# OnOfre_2ADSP.net
KiCad netlist of a schematic drawn in EAGLE
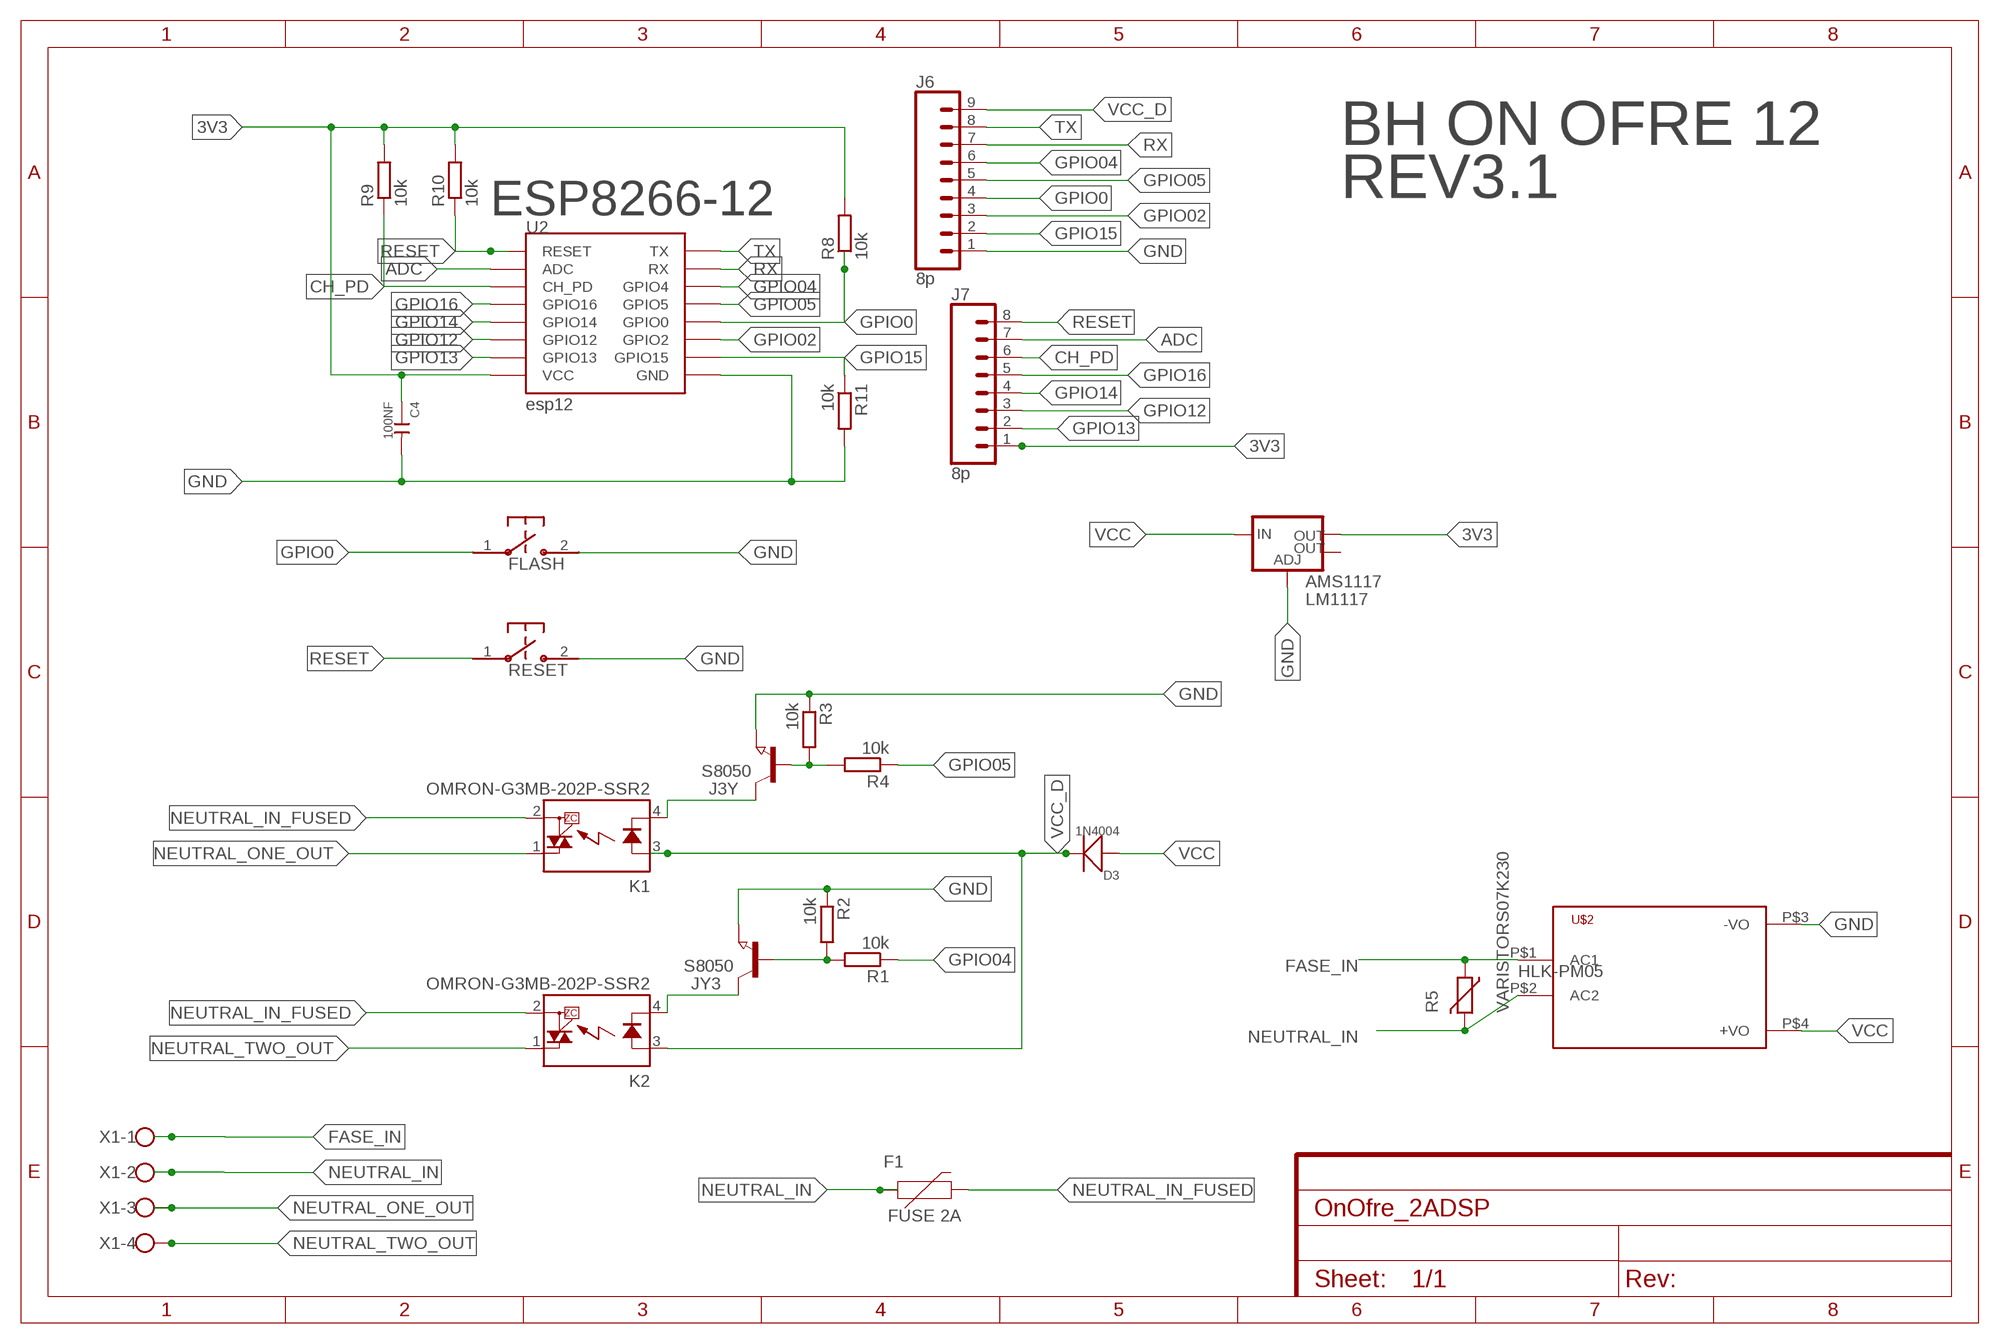
[diagram p0: schematic, sheet 1]

(export (version "E")
  (design (tool "Eeschema 10.0.6"))
  (components
    (comp (ref "AMS1117")
      (value "LM1117")
      (footprint "eagle-import:SOT223")
      (libsource (lib "eagle-import") (part "V_REG_LM1117SOT223"))
    )
    (comp (ref "C4")
      (value "100NF")
      (footprint "eagle-import:C1206")
      (fields (field (name "MPN") "CC1206KKX7RCBB102"))
      (libsource (lib "eagle-import") (part "CERAMIC-1NF-1KV-10%-X7R?(1206)"))
    )
    (comp (ref "D3")
      (value "1N4004")
      (footprint "eagle-import:DO-214AC")
      (fields (field (name "MPN") "1N4007"))
      (libsource (lib "eagle-import") (part "DIODE-GEN-PURPOSE-1KV-1A(DO-214AC)"))
    )
    (comp (ref "F1")
      (value "FUSE 2A")
      (footprint "eagle-import:PTH")
      (libsource (lib "eagle-import") (part "PPTC_PTH"))
    )
    (comp (ref "FLASH")
      (value "B3U-1000P-2P-SMD")
      (footprint "eagle-import:B3U-1000P")
      (fields
        (field (name "MANUFACTURER") "Omron")
        (field (name "MPN") "B3U-1000P")
        (field (name "SPICEPREFIX") "F")
      )
      (libsource (lib "eagle-import") (part "B3U-1000P"))
    )
    (comp (ref "J3Y")
      (value "S8050")
      (footprint "eagle-import:SOT23")
      (libsource (lib "eagle-import") (part "NPN-TRANSISTOR_SOT23"))
    )
    (comp (ref "J6")
      (value "8p")
      (footprint "eagle-import:1X09")
      (libsource (lib "eagle-import") (part "CONN_09"))
    )
    (comp (ref "J7")
      (value "8p")
      (footprint "eagle-import:1X08")
      (libsource (lib "eagle-import") (part "CONN_08{dblquote}"))
    )
    (comp (ref "JY3")
      (value "S8050")
      (footprint "eagle-import:SOT23")
      (libsource (lib "eagle-import") (part "NPN-TRANSISTOR_SOT23"))
    )
    (comp (ref "K1")
      (value "OMRON-G3MB-202P-SSR2")
      (footprint "eagle-import:OMRON-G3MB-202P-SSR")
      (fields (field (name "MPN") "S202S02F"))
      (libsource (lib "eagle-import") (part "OMRON-G3MB-202P-SSR2"))
    )
    (comp (ref "K2")
      (value "OMRON-G3MB-202P-SSR2")
      (footprint "eagle-import:OMRON-G3MB-202P-SSR")
      (fields (field (name "MPN") "S202S02F"))
      (libsource (lib "eagle-import") (part "OMRON-G3MB-202P-SSR2"))
    )
    (comp (ref "R1")
      (value "10k")
      (footprint "eagle-import:R0603")
      (libsource (lib "eagle-import") (part "R-EU_R0603"))
    )
    (comp (ref "R2")
      (value "10k")
      (footprint "eagle-import:R0603")
      (libsource (lib "eagle-import") (part "R-EU_R0603"))
    )
    (comp (ref "R3")
      (value "10k")
      (footprint "eagle-import:R0603")
      (libsource (lib "eagle-import") (part "R-EU_R0603"))
    )
    (comp (ref "R4")
      (value "10k")
      (footprint "eagle-import:R0603")
      (libsource (lib "eagle-import") (part "R-EU_R0603"))
    )
    (comp (ref "R5")
      (value "VARISTORS07K230")
      (footprint "eagle-import:S07K230")
      (libsource (lib "eagle-import") (part "VARISTORS07K230"))
    )
    (comp (ref "R8")
      (value "10k")
      (footprint "eagle-import:R0603")
      (libsource (lib "eagle-import") (part "R-EU_R0603"))
    )
    (comp (ref "R9")
      (value "10k")
      (footprint "eagle-import:R0603")
      (libsource (lib "eagle-import") (part "R-EU_R0603"))
    )
    (comp (ref "R10")
      (value "10k")
      (footprint "eagle-import:R0603")
      (libsource (lib "eagle-import") (part "R-EU_R0603"))
    )
    (comp (ref "R11")
      (value "10k")
      (footprint "eagle-import:R0603")
      (libsource (lib "eagle-import") (part "R-EU_R0603"))
    )
    (comp (ref "RESET")
      (value "B3U-1000P-2P-SMD")
      (footprint "eagle-import:B3U-1000P")
      (fields (field (name "MANUFACTURER") "Omron") (field (name "MPN") "B3U-1000P"))
      (libsource (lib "eagle-import") (part "B3U-1000P"))
    )
    (comp (ref "U$2")
      (value "HKLPM01")
      (footprint "eagle-import:HKLPM01")
      (libsource (lib "eagle-import") (part "HKLPM01"))
    )
    (comp (ref "U2")
      (value "esp12")
      (footprint "eagle-import:ESP12-SMD")
      (libsource (lib "eagle-import") (part "ESP12SMD"))
    )
    (comp (ref "X1")
      (value "W237-4")
      (footprint "eagle-import:W237-4")
      (libsource (lib "eagle-import") (part "W237-4"))
    )
  )
  (nets
    (net (code "1") (name "3V3") (class "Default")
      (node (ref "AMS1117") (pin "2") (pinfunction "OUT_2") (pintype "output"))
      (node (ref "C4") (pin "1") (pinfunction "1_1") (pintype "passive"))
      (node (ref "J7") (pin "1") (pinfunction "1_1") (pintype "passive"))
      (node (ref "R10") (pin "2") (pinfunction "2_2") (pintype "passive"))
      (node (ref "R8") (pin "2") (pinfunction "2_2") (pintype "passive"))
      (node (ref "R9") (pin "2") (pinfunction "2_2") (pintype "passive"))
      (node (ref "U2") (pin "VCC") (pinfunction "VCC_VCC") (pintype "bidirectional"))
    )
    (net (code "2") (name "ADC") (class "Default")
      (node (ref "J7") (pin "7") (pinfunction "7_7") (pintype "passive"))
      (node (ref "U2") (pin "ADC") (pinfunction "ADC_ADC") (pintype "bidirectional"))
    )
    (net (code "3") (name "CH_PD") (class "Default")
      (node (ref "J7") (pin "6") (pinfunction "6_6") (pintype "passive"))
      (node (ref "R9") (pin "1") (pinfunction "1_1") (pintype "passive"))
      (node (ref "U2") (pin "CH_PD") (pinfunction "CH_PD_CH_PD") (pintype "bidirectional"))
    )
    (net (code "4") (name "FASE_IN") (class "Default")
      (node (ref "R5") (pin "1") (pinfunction "1_1") (pintype "passive"))
      (node (ref "U$2") (pin "P$1") (pinfunction "AC1_P$1") (pintype "bidirectional"))
      (node (ref "X1") (pin "1") (pinfunction "KL_1") (pintype "passive"))
    )
    (net (code "5") (name "GND") (class "Default")
      (node (ref "AMS1117") (pin "1") (pinfunction "ADJ_1") (pintype "input"))
      (node (ref "C4") (pin "2") (pinfunction "2_2") (pintype "passive"))
      (node (ref "FLASH") (pin "2") (pinfunction "P$2_2") (pintype "passive"))
      (node (ref "J3Y") (pin "2") (pinfunction "E_2") (pintype "passive"))
      (node (ref "J6") (pin "1") (pinfunction "1_1") (pintype "passive"))
      (node (ref "JY3") (pin "2") (pinfunction "E_2") (pintype "passive"))
      (node (ref "R11") (pin "2") (pinfunction "2_2") (pintype "passive"))
      (node (ref "R2") (pin "1") (pinfunction "1_1") (pintype "passive"))
      (node (ref "R3") (pin "1") (pinfunction "1_1") (pintype "passive"))
      (node (ref "RESET") (pin "2") (pinfunction "P$2_2") (pintype "passive"))
      (node (ref "U$2") (pin "P$3") (pinfunction "-VO_P$3") (pintype "bidirectional"))
      (node (ref "U2") (pin "GND") (pinfunction "GND_GND") (pintype "bidirectional"))
    )
    (net (code "6") (name "GPIO0") (class "Default")
      (node (ref "FLASH") (pin "1") (pinfunction "P$1_1") (pintype "passive"))
      (node (ref "J6") (pin "4") (pinfunction "4_4") (pintype "passive"))
      (node (ref "R8") (pin "1") (pinfunction "1_1") (pintype "passive"))
      (node (ref "U2") (pin "GPIO0") (pinfunction "GPIO0_GPIO0") (pintype "bidirectional"))
    )
    (net (code "7") (name "GPIO02") (class "Default")
      (node (ref "J6") (pin "3") (pinfunction "3_3") (pintype "passive"))
      (node (ref "U2") (pin "GPIO2") (pinfunction "GPIO2_GPIO2") (pintype "bidirectional"))
    )
    (net (code "8") (name "GPIO04") (class "Default")
      (node (ref "J6") (pin "6") (pinfunction "6_6") (pintype "passive"))
      (node (ref "R1") (pin "1") (pinfunction "1_1") (pintype "passive"))
      (node (ref "U2") (pin "GPIO4") (pinfunction "GPIO4_GPIO4") (pintype "bidirectional"))
    )
    (net (code "9") (name "GPIO05") (class "Default")
      (node (ref "J6") (pin "5") (pinfunction "5_5") (pintype "passive"))
      (node (ref "R4") (pin "1") (pinfunction "1_1") (pintype "passive"))
      (node (ref "U2") (pin "GPIO5") (pinfunction "GPIO5_GPIO5") (pintype "bidirectional"))
    )
    (net (code "10") (name "GPIO12") (class "Default")
      (node (ref "J7") (pin "3") (pinfunction "3_3") (pintype "passive"))
      (node (ref "U2") (pin "GPIO12") (pinfunction "GPIO12_GPIO12") (pintype "bidirectional"))
    )
    (net (code "11") (name "GPIO13") (class "Default")
      (node (ref "J7") (pin "2") (pinfunction "2_2") (pintype "passive"))
      (node (ref "U2") (pin "GPIO13") (pinfunction "GPIO13_GPIO13") (pintype "bidirectional"))
    )
    (net (code "12") (name "GPIO14") (class "Default")
      (node (ref "J7") (pin "4") (pinfunction "4_4") (pintype "passive"))
      (node (ref "U2") (pin "GPIO14") (pinfunction "GPIO14_GPIO14") (pintype "bidirectional"))
    )
    (net (code "13") (name "GPIO15") (class "Default")
      (node (ref "J6") (pin "2") (pinfunction "2_2") (pintype "passive"))
      (node (ref "R11") (pin "1") (pinfunction "1_1") (pintype "passive"))
      (node (ref "U2") (pin "GPIO15") (pinfunction "GPIO15_GPIO15") (pintype "bidirectional"))
    )
    (net (code "14") (name "GPIO16") (class "Default")
      (node (ref "J7") (pin "5") (pinfunction "5_5") (pintype "passive"))
      (node (ref "U2") (pin "GPIO16") (pinfunction "GPIO16_GPIO16") (pintype "bidirectional"))
    )
    (net (code "15") (name "NEUTRAL_IN") (class "Default")
      (node (ref "F1") (pin "P$1") (pinfunction "1_P$1") (pintype "bidirectional"))
      (node (ref "R5") (pin "2") (pinfunction "2_2") (pintype "passive"))
      (node (ref "U$2") (pin "P$2") (pinfunction "AC2_P$2") (pintype "bidirectional"))
      (node (ref "X1") (pin "2") (pinfunction "KL_2") (pintype "passive"))
    )
    (net (code "16") (name "NEUTRAL_IN_FUSED") (class "Default")
      (node (ref "F1") (pin "P$2") (pinfunction "2_P$2") (pintype "bidirectional"))
      (node (ref "K1") (pin "2") (pinfunction "DS2_2") (pintype "passive"))
      (node (ref "K2") (pin "2") (pinfunction "DS2_2") (pintype "passive"))
    )
    (net (code "17") (name "NEUTRAL_ONE_OUT") (class "Default")
      (node (ref "K1") (pin "1") (pinfunction "DS1_1") (pintype "passive"))
      (node (ref "X1") (pin "3") (pinfunction "KL_3") (pintype "passive"))
    )
    (net (code "18") (name "NEUTRAL_TWO_OUT") (class "Default")
      (node (ref "K2") (pin "1") (pinfunction "DS1_1") (pintype "passive"))
      (node (ref "X1") (pin "4") (pinfunction "KL_4") (pintype "passive"))
    )
    (net (code "19") (name "Net-(J3Y-B)") (class "Default")
      (node (ref "J3Y") (pin "1") (pinfunction "B_1") (pintype "passive"))
      (node (ref "R3") (pin "2") (pinfunction "2_2") (pintype "passive"))
      (node (ref "R4") (pin "2") (pinfunction "2_2") (pintype "passive"))
    )
    (net (code "20") (name "Net-(J3Y-C)") (class "Default")
      (node (ref "J3Y") (pin "3") (pinfunction "C_3") (pintype "passive"))
      (node (ref "K1") (pin "4") (pinfunction "K_4") (pintype "passive"))
    )
    (net (code "21") (name "Net-(JY3-B)") (class "Default")
      (node (ref "JY3") (pin "1") (pinfunction "B_1") (pintype "passive"))
      (node (ref "R1") (pin "2") (pinfunction "2_2") (pintype "passive"))
      (node (ref "R2") (pin "2") (pinfunction "2_2") (pintype "passive"))
    )
    (net (code "22") (name "Net-(JY3-C)") (class "Default")
      (node (ref "JY3") (pin "3") (pinfunction "C_3") (pintype "passive"))
      (node (ref "K2") (pin "4") (pinfunction "K_4") (pintype "passive"))
    )
    (net (code "23") (name "RESET") (class "Default")
      (node (ref "J7") (pin "8") (pinfunction "8_8") (pintype "passive"))
      (node (ref "R10") (pin "1") (pinfunction "1_1") (pintype "passive"))
      (node (ref "RESET") (pin "1") (pinfunction "P$1_1") (pintype "passive"))
      (node (ref "U2") (pin "RESET") (pinfunction "RESET_RESET") (pintype "bidirectional"))
    )
    (net (code "24") (name "RX") (class "Default")
      (node (ref "J6") (pin "7") (pinfunction "7_7") (pintype "passive"))
      (node (ref "U2") (pin "RXD0") (pinfunction "RX_RXD0") (pintype "bidirectional"))
    )
    (net (code "25") (name "TX") (class "Default")
      (node (ref "J6") (pin "8") (pinfunction "8_8") (pintype "passive"))
      (node (ref "U2") (pin "TXD0") (pinfunction "TX_TXD0") (pintype "bidirectional"))
    )
    (net (code "26") (name "VCC") (class "Default")
      (node (ref "AMS1117") (pin "3") (pinfunction "IN_3") (pintype "input"))
      (node (ref "D3") (pin "1") (pinfunction "+_1") (pintype "passive"))
      (node (ref "U$2") (pin "P$4") (pinfunction "+VO_P$4") (pintype "bidirectional"))
    )
    (net (code "27") (name "VCC_D") (class "Default")
      (node (ref "D3") (pin "2") (pinfunction "-_2") (pintype "passive"))
      (node (ref "J6") (pin "9") (pinfunction "9_9") (pintype "passive"))
      (node (ref "K1") (pin "3") (pinfunction "A_3") (pintype "passive"))
      (node (ref "K2") (pin "3") (pinfunction "A_3") (pintype "passive"))
    )
    (net (code "28") (name "unconnected-(AMS1117-OUT-Pad4)") (class "Default")
      (node (ref "AMS1117") (pin "4") (pinfunction "OUT_4") (pintype "output"))
    )
  )
)
